# lightswitch_controller.net
KiCad netlist of a schematic drawn in Altium Designer
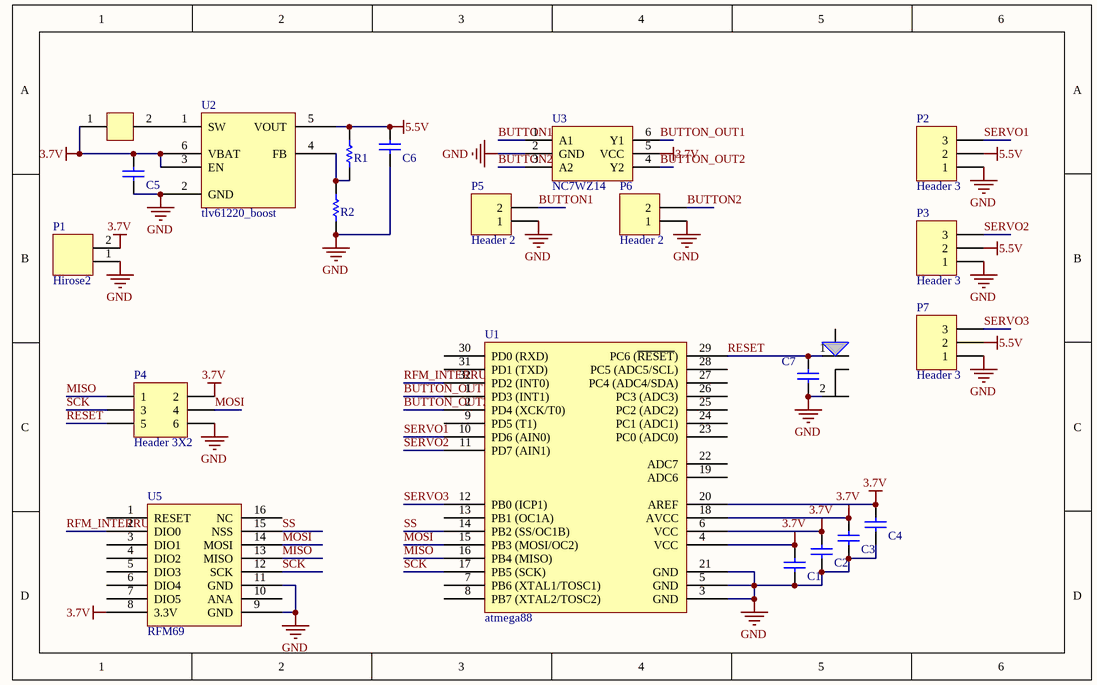
[diagram p0: lightswitch_controller.SchDoc]

(export (version "E")
  (design (tool "Eeschema 10.0.6"))
  (components
    (comp (ref "C1")
      (value "0.1uF")
      (footprint "CAPC0603(1608)100_L")
      (description "CAP 100nF 10V ±20% 0603 (1608 Metric) Thickness 1mm SMD")
      (fields (field (name "TOLERANCE") "±20%"))
      (libsource (lib "Altium Content Vault") (part "CMP-1035-02581-1"))
    )
    (comp (ref "C2")
      (value "0.1uF")
      (footprint "CAPC0603(1608)100_L")
      (description "CAP 100nF 10V ±20% 0603 (1608 Metric) Thickness 1mm SMD")
      (fields (field (name "TOLERANCE") "±20%"))
      (libsource (lib "Altium Content Vault") (part "CMP-1035-02581-1"))
    )
    (comp (ref "C3")
      (value "0.1uF")
      (footprint "CAPC0603(1608)100_L")
      (description "CAP 100nF 10V ±20% 0603 (1608 Metric) Thickness 1mm SMD")
      (fields (field (name "TOLERANCE") "±20%"))
      (libsource (lib "Altium Content Vault") (part "CMP-1035-02581-1"))
    )
    (comp (ref "C4")
      (value "CAP 100nF 10V 0603(1608)")
      (footprint "CAPC0603(1608)100_L")
      (description "CAP 100nF 10V ±20% 0603 (1608 Metric) Thickness 1mm SMD")
      (fields (field (name "TOLERANCE") "±20%"))
      (libsource (lib "Altium Content Vault") (part "CMP-1035-02581-1"))
    )
    (comp (ref "C5")
      (value "10uF")
      (footprint "CAPC0603(1608)100_L")
      (description "CAP 10uF 10V ±10% 0603 (1608 Metric) Thickness 1mm SMD")
      (fields (field (name "TOLERANCE") "±10%"))
      (libsource (lib "Altium Content Vault") (part "CMP-1035-02799-1"))
    )
    (comp (ref "C6")
      (value "10uF")
      (footprint "CAPC0603(1608)100_L")
      (description "CAP 10uF 10V ±10% 0603 (1608 Metric) Thickness 1mm SMD")
      (fields (field (name "TOLERANCE") "±10%"))
      (libsource (lib "Altium Content Vault") (part "CMP-1035-02799-1"))
    )
    (comp (ref "C7")
      (value "10nF")
      (footprint "CAPC0603(1608)100_L")
      (description "CAP 10nF 10V ±2% 0603 (1608 Metric) Thickness 1mm SMD")
      (fields (field (name "TOLERANCE") "±2%"))
      (libsource (lib "Altium Content Vault") (part "CMP-1035-02304-1"))
    )
    (comp (ref "L1")
      (value "TYS6045_inductor")
      (footprint "TYS6045")
      (libsource (lib "Integrated_Library") (part "TYS6045_inductor"))
    )
    (comp (ref "P1")
      (value "Hirose2")
      (footprint "DF3A-2P-2DS")
      (libsource (lib "Integrated_Library") (part "Hirose2"))
    )
    (comp (ref "P2")
      (value "Header 3")
      (footprint "HDR1X3")
      (description "Header, 3-Pin")
      (fields (field (name "PUBLISHER") "Altium Limited"))
      (libsource (lib "Miscellaneous Connectors") (part "Header 3"))
    )
    (comp (ref "P3")
      (value "Header 3")
      (footprint "HDR1X3")
      (description "Header, 3-Pin")
      (fields (field (name "PUBLISHER") "Altium Limited"))
      (libsource (lib "Miscellaneous Connectors") (part "Header 3"))
    )
    (comp (ref "P4")
      (value "Header 3X2")
      (footprint "HDR2X3")
      (description "Header, 3-Pin, Dual row")
      (fields (field (name "PUBLISHER") "Altium Limited"))
      (libsource (lib "Miscellaneous Connectors") (part "Header 3X2"))
    )
    (comp (ref "P5")
      (value "Header 2")
      (footprint "HDR1X2")
      (description "Header, 2-Pin")
      (fields (field (name "PUBLISHER") "Altium Limited"))
      (libsource (lib "Miscellaneous Connectors") (part "Header 2"))
    )
    (comp (ref "P6")
      (value "Header 2")
      (footprint "HDR1X2")
      (description "Header, 2-Pin")
      (fields (field (name "PUBLISHER") "Altium Limited"))
      (libsource (lib "Miscellaneous Connectors") (part "Header 2"))
    )
    (comp (ref "P7")
      (value "Header 3")
      (footprint "HDR1X3")
      (description "Header, 3-Pin")
      (fields (field (name "PUBLISHER") "Altium Limited"))
      (libsource (lib "Miscellaneous Connectors") (part "Header 3"))
    )
    (comp (ref "R1")
      (value "1.8M")
      (footprint "RESC0603(1608)_L")
      (description "1M8 0.1W 5% 0603 (1608 Metric)  SMD")
      (fields (field (name "TOLERANCE") "5 %") (field (name "POWER") "0.1 W"))
      (libsource (lib "Altium Content Vault") (part "CMP-1012-00152-1"))
    )
    (comp (ref "R2")
      (value "180K")
      (footprint "RESC0603(1608)_L")
      (description "180K 0.1W 5% 0603 (1608 Metric)  SMD")
      (fields (field (name "POWER") "0.1 W") (field (name "TOLERANCE") "5 %"))
      (libsource (lib "Altium Content Vault") (part "CMP-1012-00128-1"))
    )
    (comp (ref "S1")
      (value "2lead_low_profile_switch")
      (footprint "2lead_low_profile_switch")
      (libsource (lib "Integrated_Library") (part "2lead_low_profile_switch"))
    )
    (comp (ref "U1")
      (value "atmega88")
      (footprint "atmega44/88/168")
      (libsource (lib "Integrated_Library") (part "atmega88"))
    )
    (comp (ref "U2")
      (value "tlv61220_boost")
      (footprint "TLV61220_BOOST")
      (libsource (lib "Integrated_Library") (part "tlv61220_boost"))
    )
    (comp (ref "U3")
      (value "NC7WZ14")
      (footprint "NC7WZ14")
      (libsource (lib "Integrated_Library") (part "NC7WZ14"))
    )
    (comp (ref "U5")
      (value "RFM69")
      (footprint "RFM69")
      (libsource (lib "Integrated_Library") (part "RFM69"))
    )
  )
  (nets
    (net (code "1") (name "/BUTTON1") (class "Default")
      (node (ref "P5") (pin "2") (pinfunction "2_2") (pintype "passive"))
      (node (ref "U3") (pin "1") (pinfunction "A1_1") (pintype "passive"))
    )
    (net (code "2") (name "/BUTTON2") (class "Default")
      (node (ref "P6") (pin "2") (pinfunction "2_2") (pintype "passive"))
      (node (ref "U3") (pin "3") (pinfunction "A2_3") (pintype "passive"))
    )
    (net (code "3") (name "/BUTTON_OUT1") (class "Default")
      (node (ref "U1") (pin "1") (pinfunction "PD3_(INT1)_1") (pintype "passive"))
      (node (ref "U3") (pin "6") (pinfunction "Y1_6") (pintype "passive"))
    )
    (net (code "4") (name "/BUTTON_OUT2") (class "Default")
      (node (ref "U1") (pin "2") (pinfunction "PD4_(XCK/T0)_2") (pintype "passive"))
      (node (ref "U3") (pin "4") (pinfunction "Y2_4") (pintype "passive"))
    )
    (net (code "5") (name "/MISO") (class "Default")
      (node (ref "P4") (pin "1") (pinfunction "1_1") (pintype "passive"))
      (node (ref "U1") (pin "16") (pinfunction "PB4_(MISO)_16") (pintype "passive"))
      (node (ref "U5") (pin "13") (pinfunction "MISO_13") (pintype "passive"))
    )
    (net (code "6") (name "/MOSI") (class "Default")
      (node (ref "P4") (pin "4") (pinfunction "4_4") (pintype "passive"))
      (node (ref "U1") (pin "15") (pinfunction "PB3_(MOSI/OC2)_15") (pintype "passive"))
      (node (ref "U5") (pin "14") (pinfunction "MOSI_14") (pintype "passive"))
    )
    (net (code "7") (name "/RESET") (class "Default")
      (node (ref "C7") (pin "2") (pinfunction "2_2") (pintype "passive"))
      (node (ref "P4") (pin "5") (pinfunction "5_5") (pintype "passive"))
      (node (ref "S1") (pin "1") (pinfunction "GND_1") (pintype "passive"))
      (node (ref "U1") (pin "29") (pinfunction "PC6_(~{RESET})_29") (pintype "passive"))
    )
    (net (code "8") (name "/RFM_INTERRUPT") (class "Default")
      (node (ref "U1") (pin "32") (pinfunction "PD2_(INT0)_32") (pintype "passive"))
      (node (ref "U5") (pin "2") (pinfunction "DIO0_2") (pintype "passive"))
    )
    (net (code "9") (name "/SCK") (class "Default")
      (node (ref "P4") (pin "3") (pinfunction "3_3") (pintype "passive"))
      (node (ref "U1") (pin "17") (pinfunction "PB5_(SCK)_17") (pintype "passive"))
      (node (ref "U5") (pin "12") (pinfunction "SCK_12") (pintype "passive"))
    )
    (net (code "10") (name "/SERVO1") (class "Default")
      (node (ref "P2") (pin "3") (pinfunction "3_3") (pintype "passive"))
      (node (ref "U1") (pin "10") (pinfunction "PD6_(AIN0)_10") (pintype "passive"))
    )
    (net (code "11") (name "/SERVO2") (class "Default")
      (node (ref "P3") (pin "3") (pinfunction "3_3") (pintype "passive"))
      (node (ref "U1") (pin "11") (pinfunction "PD7_(AIN1)_11") (pintype "passive"))
    )
    (net (code "12") (name "/SERVO3") (class "Default")
      (node (ref "P7") (pin "3") (pinfunction "3_3") (pintype "passive"))
      (node (ref "U1") (pin "12") (pinfunction "PB0_(ICP1)_12") (pintype "passive"))
    )
    (net (code "13") (name "/SS") (class "Default")
      (node (ref "U1") (pin "14") (pinfunction "PB2_(SS/OC1B)_14") (pintype "passive"))
      (node (ref "U5") (pin "15") (pinfunction "NSS_15") (pintype "passive"))
    )
    (net (code "14") (name "3.7V") (class "Default")
      (node (ref "C1") (pin "2") (pinfunction "2_2") (pintype "passive"))
      (node (ref "C2") (pin "2") (pinfunction "2_2") (pintype "passive"))
      (node (ref "C3") (pin "2") (pinfunction "2_2") (pintype "passive"))
      (node (ref "C4") (pin "2") (pinfunction "2_2") (pintype "passive"))
      (node (ref "C5") (pin "2") (pinfunction "2_2") (pintype "passive"))
      (node (ref "L1") (pin "1") (pintype "passive"))
      (node (ref "P1") (pin "2") (pintype "passive"))
      (node (ref "P4") (pin "2") (pinfunction "2_2") (pintype "passive"))
      (node (ref "U1") (pin "18") (pinfunction "AVCC_18") (pintype "passive"))
      (node (ref "U1") (pin "20") (pinfunction "AREF_20") (pintype "passive"))
      (node (ref "U1") (pin "4") (pinfunction "VCC_4") (pintype "passive"))
      (node (ref "U1") (pin "6") (pinfunction "VCC_6") (pintype "passive"))
      (node (ref "U2") (pin "3") (pinfunction "EN_3") (pintype "passive"))
      (node (ref "U2") (pin "6") (pinfunction "VBAT_6") (pintype "passive"))
      (node (ref "U3") (pin "5") (pinfunction "VCC_5") (pintype "passive"))
      (node (ref "U5") (pin "8") (pinfunction "3.3V_8") (pintype "passive"))
    )
    (net (code "15") (name "5.5V") (class "Default")
      (node (ref "C6") (pin "2") (pinfunction "2_2") (pintype "passive"))
      (node (ref "P2") (pin "2") (pinfunction "2_2") (pintype "passive"))
      (node (ref "P3") (pin "2") (pinfunction "2_2") (pintype "passive"))
      (node (ref "P7") (pin "2") (pinfunction "2_2") (pintype "passive"))
      (node (ref "R1") (pin "2") (pinfunction "2_2") (pintype "passive"))
      (node (ref "U2") (pin "5") (pinfunction "VOUT_5") (pintype "passive"))
    )
    (net (code "16") (name "GND") (class "Default")
      (node (ref "C1") (pin "1") (pinfunction "1_1") (pintype "passive"))
      (node (ref "C2") (pin "1") (pinfunction "1_1") (pintype "passive"))
      (node (ref "C3") (pin "1") (pinfunction "1_1") (pintype "passive"))
      (node (ref "C4") (pin "1") (pinfunction "1_1") (pintype "passive"))
      (node (ref "C5") (pin "1") (pinfunction "1_1") (pintype "passive"))
      (node (ref "C6") (pin "1") (pinfunction "1_1") (pintype "passive"))
      (node (ref "C7") (pin "1") (pinfunction "1_1") (pintype "passive"))
      (node (ref "P1") (pin "1") (pintype "passive"))
      (node (ref "P2") (pin "1") (pinfunction "1_1") (pintype "passive"))
      (node (ref "P3") (pin "1") (pinfunction "1_1") (pintype "passive"))
      (node (ref "P4") (pin "6") (pinfunction "6_6") (pintype "passive"))
      (node (ref "P5") (pin "1") (pinfunction "1_1") (pintype "passive"))
      (node (ref "P6") (pin "1") (pinfunction "1_1") (pintype "passive"))
      (node (ref "P7") (pin "1") (pinfunction "1_1") (pintype "passive"))
      (node (ref "R2") (pin "1") (pinfunction "1_1") (pintype "passive"))
      (node (ref "S1") (pin "2") (pinfunction "GND_2") (pintype "passive"))
      (node (ref "U1") (pin "21") (pinfunction "GND_21") (pintype "passive"))
      (node (ref "U1") (pin "3") (pinfunction "GND_3") (pintype "passive"))
      (node (ref "U1") (pin "5") (pinfunction "GND_5") (pintype "passive"))
      (node (ref "U2") (pin "2") (pinfunction "GND_2") (pintype "passive"))
      (node (ref "U3") (pin "2") (pinfunction "GND_2") (pintype "passive"))
      (node (ref "U5") (pin "11") (pinfunction "GND_11") (pintype "passive"))
      (node (ref "U5") (pin "9") (pinfunction "GND_9") (pintype "passive"))
    )
    (net (code "17") (name "Net-(U2-FB)") (class "Default")
      (node (ref "R1") (pin "1") (pinfunction "1_1") (pintype "passive"))
      (node (ref "R2") (pin "2") (pinfunction "2_2") (pintype "passive"))
      (node (ref "U2") (pin "4") (pinfunction "FB_4") (pintype "passive"))
    )
    (net (code "18") (name "Net-(U2-SW)") (class "Default")
      (node (ref "L1") (pin "2") (pintype "passive"))
      (node (ref "U2") (pin "1") (pinfunction "SW_1") (pintype "passive"))
    )
    (net (code "19") (name "unconnected-(U1-ADC6-Pad19)") (class "Default")
      (node (ref "U1") (pin "19") (pinfunction "ADC6_19") (pintype "passive"))
    )
    (net (code "20") (name "unconnected-(U1-ADC7-Pad22)") (class "Default")
      (node (ref "U1") (pin "22") (pinfunction "ADC7_22") (pintype "passive"))
    )
    (net (code "21") (name "unconnected-(U1-PB1_(OC1A)-Pad13)") (class "Default")
      (node (ref "U1") (pin "13") (pinfunction "PB1_(OC1A)_13") (pintype "passive"))
    )
    (net (code "22") (name "unconnected-(U1-PB6_(XTAL1{slash}TOSC1)-Pad7)") (class "Default")
      (node (ref "U1") (pin "7") (pinfunction "PB6_(XTAL1/TOSC1)_7") (pintype "passive"))
    )
    (net (code "23") (name "unconnected-(U1-PB7_(XTAL2{slash}TOSC2)-Pad8)") (class "Default")
      (node (ref "U1") (pin "8") (pinfunction "PB7_(XTAL2/TOSC2)_8") (pintype "passive"))
    )
    (net (code "24") (name "unconnected-(U1-PC0_(ADC0)-Pad23)") (class "Default")
      (node (ref "U1") (pin "23") (pinfunction "PC0_(ADC0)_23") (pintype "passive"))
    )
    (net (code "25") (name "unconnected-(U1-PC1_(ADC1)-Pad24)") (class "Default")
      (node (ref "U1") (pin "24") (pinfunction "PC1_(ADC1)_24") (pintype "passive"))
    )
    (net (code "26") (name "unconnected-(U1-PC2_(ADC2)-Pad25)") (class "Default")
      (node (ref "U1") (pin "25") (pinfunction "PC2_(ADC2)_25") (pintype "passive"))
    )
    (net (code "27") (name "unconnected-(U1-PC3_(ADC3)-Pad26)") (class "Default")
      (node (ref "U1") (pin "26") (pinfunction "PC3_(ADC3)_26") (pintype "passive"))
    )
    (net (code "28") (name "unconnected-(U1-PC4_(ADC4{slash}SDA)-Pad27)") (class "Default")
      (node (ref "U1") (pin "27") (pinfunction "PC4_(ADC4/SDA)_27") (pintype "passive"))
    )
    (net (code "29") (name "unconnected-(U1-PC5_(ADC5{slash}SCL)-Pad28)") (class "Default")
      (node (ref "U1") (pin "28") (pinfunction "PC5_(ADC5/SCL)_28") (pintype "passive"))
    )
    (net (code "30") (name "unconnected-(U1-PD0_(RXD)-Pad30)") (class "Default")
      (node (ref "U1") (pin "30") (pinfunction "PD0_(RXD)_30") (pintype "passive"))
    )
    (net (code "31") (name "unconnected-(U1-PD1_(TXD)-Pad31)") (class "Default")
      (node (ref "U1") (pin "31") (pinfunction "PD1_(TXD)_31") (pintype "passive"))
    )
    (net (code "32") (name "unconnected-(U1-PD5_(T1)-Pad9)") (class "Default")
      (node (ref "U1") (pin "9") (pinfunction "PD5_(T1)_9") (pintype "passive"))
    )
    (net (code "33") (name "unconnected-(U5-ANA-Pad10)") (class "Default")
      (node (ref "U5") (pin "10") (pinfunction "ANA_10") (pintype "passive"))
    )
    (net (code "34") (name "unconnected-(U5-DIO1-Pad3)") (class "Default")
      (node (ref "U5") (pin "3") (pinfunction "DIO1_3") (pintype "passive"))
    )
    (net (code "35") (name "unconnected-(U5-DIO2-Pad4)") (class "Default")
      (node (ref "U5") (pin "4") (pinfunction "DIO2_4") (pintype "passive"))
    )
    (net (code "36") (name "unconnected-(U5-DIO3-Pad5)") (class "Default")
      (node (ref "U5") (pin "5") (pinfunction "DIO3_5") (pintype "passive"))
    )
    (net (code "37") (name "unconnected-(U5-DIO4-Pad6)") (class "Default")
      (node (ref "U5") (pin "6") (pinfunction "DIO4_6") (pintype "passive"))
    )
    (net (code "38") (name "unconnected-(U5-DIO5-Pad7)") (class "Default")
      (node (ref "U5") (pin "7") (pinfunction "DIO5_7") (pintype "passive"))
    )
    (net (code "39") (name "unconnected-(U5-NC-Pad16)") (class "Default")
      (node (ref "U5") (pin "16") (pinfunction "NC_16") (pintype "passive"))
    )
    (net (code "40") (name "unconnected-(U5-RESET-Pad1)") (class "Default")
      (node (ref "U5") (pin "1") (pinfunction "RESET_1") (pintype "passive"))
    )
  )
)
